# SSD_M_2_B-Key.net
KiCad netlist of a schematic drawn in Altium Designer
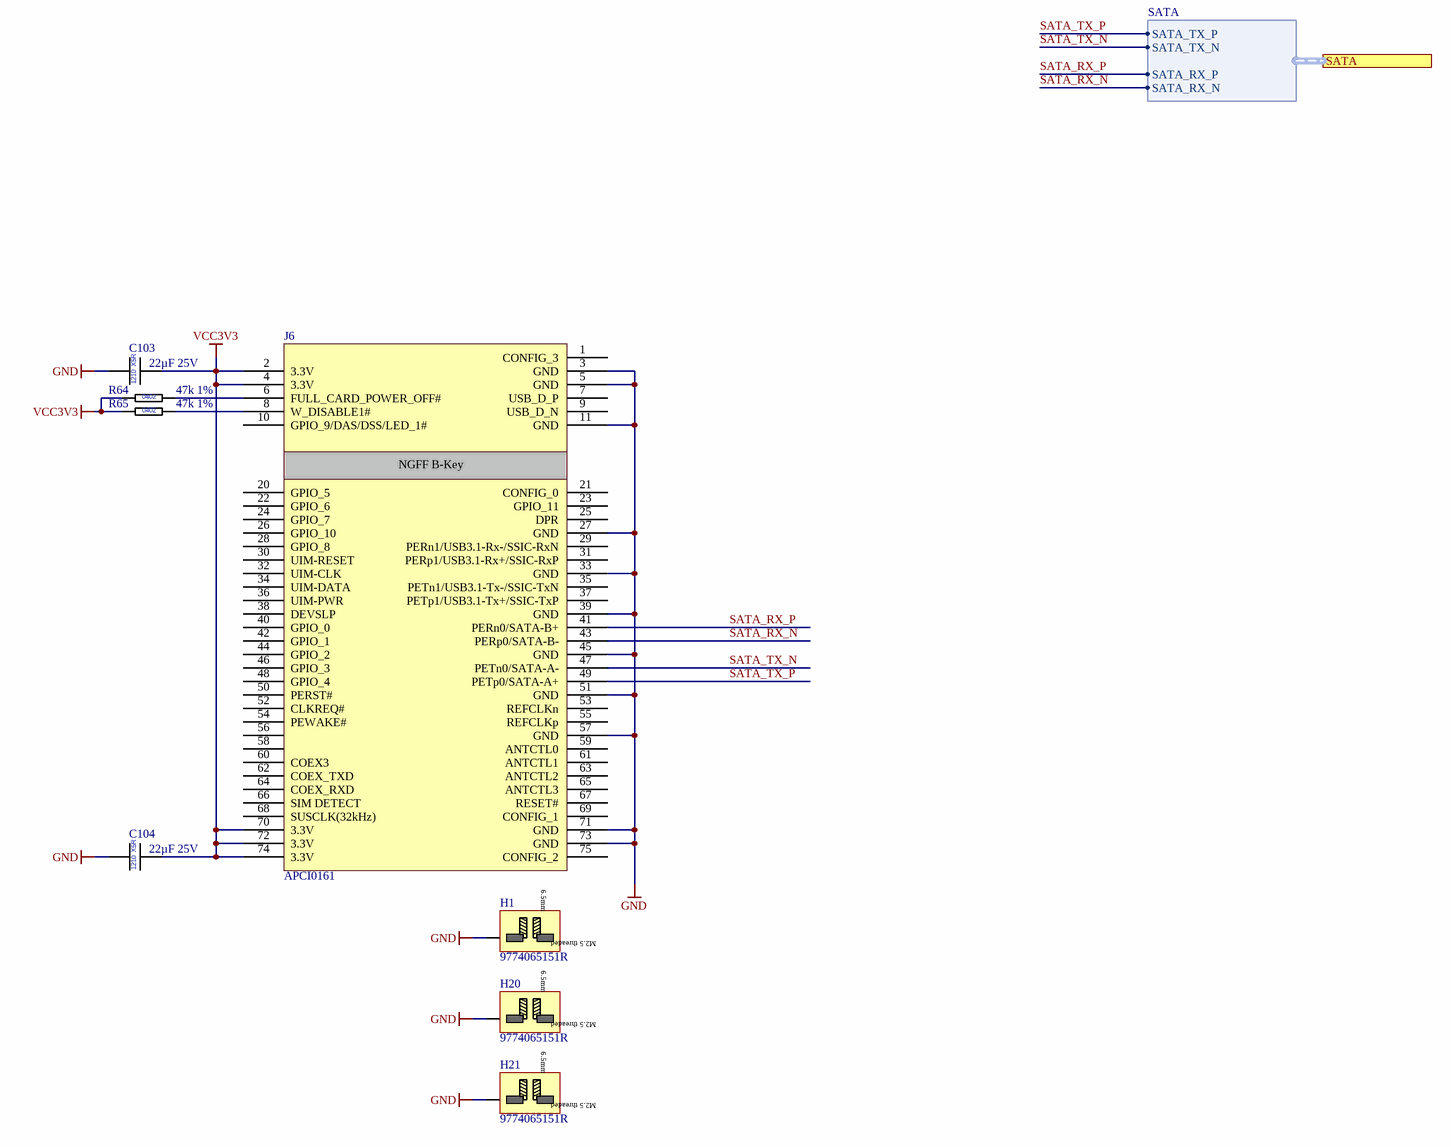
[diagram p0: SSD M.2_B-Key.SchDoc]

(export (version "E")
  (design (tool "Eeschema 10.0.6"))
  (components
    (comp (ref "C103")
      (value "22µF 25V")
      (footprint "Cap:CAP_1210")
      (description "Multilayer Ceramic Capacitors MLCC - SMD/SMT 1210 25VDC")
      (libsource (lib "Cap") (part "CAP_1210_22µF_25V"))
    )
    (comp (ref "C104")
      (value "22µF 25V")
      (footprint "Cap:CAP_1210")
      (description "Multilayer Ceramic Capacitors MLCC - SMD/SMT 1210 25VDC")
      (libsource (lib "Cap") (part "CAP_1210_22µF_25V"))
    )
    (comp (ref "H1")
      (value "9774065151R")
      (footprint "Electro_Mech:9774065151R")
      (description "Würth Standoff M2.5 h:6.5mm 9774065151R")
      (libsource (lib "Electro_Mech") (part "Würth Standoff M2.5 h{colon}6.5mm"))
    )
    (comp (ref "H20")
      (value "9774065151R")
      (footprint "Electro_Mech:9774065151R")
      (description "Würth Standoff M2.5 h:6.5mm 9774065151R")
      (libsource (lib "Electro_Mech") (part "Würth Standoff M2.5 h{colon}6.5mm"))
    )
    (comp (ref "H21")
      (value "9774065151R")
      (footprint "Electro_Mech:9774065151R")
      (description "Würth Standoff M2.5 h:6.5mm 9774065151R")
      (libsource (lib "Electro_Mech") (part "Würth Standoff M2.5 h{colon}6.5mm"))
    )
    (comp (ref "J6")
      (value "APCI0161")
      (footprint "conn:APCI0161-P001A")
      (description "NGFF B-Key Card Edge Connector 8.5mm Height")
      (libsource (lib "Conn") (part "APCI0161-NGFF B-Key Card Edge Connector 8.5mm Height"))
    )
    (comp (ref "R64")
      (value "47k 1%")
      (footprint "Res:RES_0402_L")
      (description "Thick Film Resistors - SMD 47kOhm 1%")
      (libsource (lib "Res") (part "RES_0402_47k_1%"))
    )
    (comp (ref "R65")
      (value "47k 1%")
      (footprint "Res:RES_0402_L")
      (description "Thick Film Resistors - SMD 47kOhm 1%")
      (libsource (lib "Res") (part "RES_0402_47k_1%"))
    )
  )
  (nets
    (net (code "2") (name "/SATA_RX_N") (class "Default")
      (node (ref "J6") (pin "43") (pinfunction "PERp0/SATA-B-_43") (pintype "passive"))
    )
    (net (code "3") (name "/SATA_RX_P") (class "Default")
      (node (ref "J6") (pin "41") (pinfunction "PERn0/SATA-B+_41") (pintype "passive"))
    )
    (net (code "4") (name "/SATA_TX_N") (class "Default")
      (node (ref "J6") (pin "47") (pinfunction "PETn0/SATA-A-_47") (pintype "passive"))
    )
    (net (code "5") (name "/SATA_TX_P") (class "Default")
      (node (ref "J6") (pin "49") (pinfunction "PETp0/SATA-A+_49") (pintype "passive"))
    )
    (net (code "7") (name "GND") (class "Default")
      (node (ref "C103") (pin "1") (pinfunction "1_1") (pintype "passive"))
      (node (ref "C104") (pin "1") (pinfunction "1_1") (pintype "passive"))
      (node (ref "H1") (pin "1") (pinfunction "1_1") (pintype "passive"))
      (node (ref "H20") (pin "1") (pinfunction "1_1") (pintype "passive"))
      (node (ref "H21") (pin "1") (pinfunction "1_1") (pintype "passive"))
      (node (ref "J6") (pin "11") (pinfunction "GND_11") (pintype "passive"))
      (node (ref "J6") (pin "27") (pinfunction "GND_27") (pintype "passive"))
      (node (ref "J6") (pin "3") (pinfunction "GND_3") (pintype "passive"))
      (node (ref "J6") (pin "33") (pinfunction "GND_33") (pintype "passive"))
      (node (ref "J6") (pin "39") (pinfunction "GND_39") (pintype "passive"))
      (node (ref "J6") (pin "45") (pinfunction "GND_45") (pintype "passive"))
      (node (ref "J6") (pin "5") (pinfunction "GND_5") (pintype "passive"))
      (node (ref "J6") (pin "51") (pinfunction "GND_51") (pintype "passive"))
      (node (ref "J6") (pin "57") (pinfunction "GND_57") (pintype "passive"))
      (node (ref "J6") (pin "71") (pinfunction "GND_71") (pintype "passive"))
      (node (ref "J6") (pin "73") (pinfunction "GND_73") (pintype "passive"))
    )
    (net (code "8") (name "Net-(J6-FULL_CARD_POWER_OFF#)") (class "Default")
      (node (ref "J6") (pin "6") (pinfunction "FULL_CARD_POWER_OFF#_6") (pintype "passive"))
      (node (ref "R64") (pin "2") (pinfunction "2_2") (pintype "passive"))
    )
    (net (code "9") (name "Net-(J6-W_DISABLE1#)") (class "Default")
      (node (ref "J6") (pin "8") (pinfunction "W_DISABLE1#_8") (pintype "passive"))
      (node (ref "R65") (pin "2") (pinfunction "2_2") (pintype "passive"))
    )
    (net (code "10") (name "VCC3V3") (class "Default")
      (node (ref "C103") (pin "2") (pinfunction "2_2") (pintype "passive"))
      (node (ref "C104") (pin "2") (pinfunction "2_2") (pintype "passive"))
      (node (ref "J6") (pin "2") (pinfunction "3.3V_2") (pintype "passive"))
      (node (ref "J6") (pin "4") (pinfunction "3.3V_4") (pintype "passive"))
      (node (ref "J6") (pin "70") (pinfunction "3.3V_70") (pintype "passive"))
      (node (ref "J6") (pin "72") (pinfunction "3.3V_72") (pintype "passive"))
      (node (ref "J6") (pin "74") (pinfunction "3.3V_74") (pintype "passive"))
      (node (ref "R64") (pin "1") (pinfunction "1_1") (pintype "passive"))
      (node (ref "R65") (pin "1") (pinfunction "1_1") (pintype "passive"))
    )
    (net (code "11") (name "unconnected-(J6-ANTCTL0-Pad59)") (class "Default")
      (node (ref "J6") (pin "59") (pinfunction "ANTCTL0_59") (pintype "passive"))
    )
    (net (code "12") (name "unconnected-(J6-ANTCTL1-Pad61)") (class "Default")
      (node (ref "J6") (pin "61") (pinfunction "ANTCTL1_61") (pintype "passive"))
    )
    (net (code "13") (name "unconnected-(J6-ANTCTL2-Pad63)") (class "Default")
      (node (ref "J6") (pin "63") (pinfunction "ANTCTL2_63") (pintype "passive"))
    )
    (net (code "14") (name "unconnected-(J6-ANTCTL3-Pad65)") (class "Default")
      (node (ref "J6") (pin "65") (pinfunction "ANTCTL3_65") (pintype "passive"))
    )
    (net (code "15") (name "unconnected-(J6-CLKREQ#-Pad52)") (class "Default")
      (node (ref "J6") (pin "52") (pinfunction "CLKREQ#_52") (pintype "passive"))
    )
    (net (code "16") (name "unconnected-(J6-COEX3-Pad60)") (class "Default")
      (node (ref "J6") (pin "60") (pinfunction "COEX3_60") (pintype "passive"))
    )
    (net (code "17") (name "unconnected-(J6-COEX_RXD-Pad64)") (class "Default")
      (node (ref "J6") (pin "64") (pinfunction "COEX_RXD_64") (pintype "passive"))
    )
    (net (code "18") (name "unconnected-(J6-COEX_TXD-Pad62)") (class "Default")
      (node (ref "J6") (pin "62") (pinfunction "COEX_TXD_62") (pintype "passive"))
    )
    (net (code "19") (name "unconnected-(J6-CONFIG_0-Pad21)") (class "Default")
      (node (ref "J6") (pin "21") (pinfunction "CONFIG_0_21") (pintype "passive"))
    )
    (net (code "20") (name "unconnected-(J6-CONFIG_1-Pad69)") (class "Default")
      (node (ref "J6") (pin "69") (pinfunction "CONFIG_1_69") (pintype "passive"))
    )
    (net (code "21") (name "unconnected-(J6-CONFIG_2-Pad75)") (class "Default")
      (node (ref "J6") (pin "75") (pinfunction "CONFIG_2_75") (pintype "passive"))
    )
    (net (code "22") (name "unconnected-(J6-CONFIG_3-Pad1)") (class "Default")
      (node (ref "J6") (pin "1") (pinfunction "CONFIG_3_1") (pintype "passive"))
    )
    (net (code "23") (name "unconnected-(J6-DEVSLP-Pad38)") (class "Default")
      (node (ref "J6") (pin "38") (pinfunction "DEVSLP_38") (pintype "passive"))
    )
    (net (code "24") (name "unconnected-(J6-DPR-Pad25)") (class "Default")
      (node (ref "J6") (pin "25") (pinfunction "DPR_25") (pintype "passive"))
    )
    (net (code "25") (name "unconnected-(J6-GPIO_0-Pad40)") (class "Default")
      (node (ref "J6") (pin "40") (pinfunction "GPIO_0_40") (pintype "passive"))
    )
    (net (code "26") (name "unconnected-(J6-GPIO_1-Pad42)") (class "Default")
      (node (ref "J6") (pin "42") (pinfunction "GPIO_1_42") (pintype "passive"))
    )
    (net (code "27") (name "unconnected-(J6-GPIO_2-Pad44)") (class "Default")
      (node (ref "J6") (pin "44") (pinfunction "GPIO_2_44") (pintype "passive"))
    )
    (net (code "28") (name "unconnected-(J6-GPIO_3-Pad46)") (class "Default")
      (node (ref "J6") (pin "46") (pinfunction "GPIO_3_46") (pintype "passive"))
    )
    (net (code "29") (name "unconnected-(J6-GPIO_4-Pad48)") (class "Default")
      (node (ref "J6") (pin "48") (pinfunction "GPIO_4_48") (pintype "passive"))
    )
    (net (code "30") (name "unconnected-(J6-GPIO_5-Pad20)") (class "Default")
      (node (ref "J6") (pin "20") (pinfunction "GPIO_5_20") (pintype "passive"))
    )
    (net (code "31") (name "unconnected-(J6-GPIO_6-Pad22)") (class "Default")
      (node (ref "J6") (pin "22") (pinfunction "GPIO_6_22") (pintype "passive"))
    )
    (net (code "32") (name "unconnected-(J6-GPIO_7-Pad24)") (class "Default")
      (node (ref "J6") (pin "24") (pinfunction "GPIO_7_24") (pintype "passive"))
    )
    (net (code "33") (name "unconnected-(J6-GPIO_8-Pad28)") (class "Default")
      (node (ref "J6") (pin "28") (pinfunction "GPIO_8_28") (pintype "passive"))
    )
    (net (code "34") (name "unconnected-(J6-GPIO_9{slash}DAS{slash}DSS{slash}LED_1#-Pad10)") (class "Default")
      (node (ref "J6") (pin "10") (pinfunction "GPIO_9/DAS/DSS/LED_1#_10") (pintype "passive"))
    )
    (net (code "35") (name "unconnected-(J6-GPIO_10-Pad26)") (class "Default")
      (node (ref "J6") (pin "26") (pinfunction "GPIO_10_26") (pintype "passive"))
    )
    (net (code "36") (name "unconnected-(J6-GPIO_11-Pad23)") (class "Default")
      (node (ref "J6") (pin "23") (pinfunction "GPIO_11_23") (pintype "passive"))
    )
    (net (code "37") (name "unconnected-(J6-PERST#-Pad50)") (class "Default")
      (node (ref "J6") (pin "50") (pinfunction "PERST#_50") (pintype "passive"))
    )
    (net (code "38") (name "unconnected-(J6-PERn1{slash}USB3.1-Rx-{slash}SSIC-RxN-Pad29)") (class "Default")
      (node (ref "J6") (pin "29") (pinfunction "PERn1/USB3.1-Rx-/SSIC-RxN_29") (pintype "passive"))
    )
    (net (code "39") (name "unconnected-(J6-PERp1{slash}USB3.1-Rx+{slash}SSIC-RxP-Pad31)") (class "Default")
      (node (ref "J6") (pin "31") (pinfunction "PERp1/USB3.1-Rx+/SSIC-RxP_31") (pintype "passive"))
    )
    (net (code "40") (name "unconnected-(J6-PETn1{slash}USB3.1-Tx-{slash}SSIC-TxN-Pad35)") (class "Default")
      (node (ref "J6") (pin "35") (pinfunction "PETn1/USB3.1-Tx-/SSIC-TxN_35") (pintype "passive"))
    )
    (net (code "41") (name "unconnected-(J6-PETp1{slash}USB3.1-Tx+{slash}SSIC-TxP-Pad37)") (class "Default")
      (node (ref "J6") (pin "37") (pinfunction "PETp1/USB3.1-Tx+/SSIC-TxP_37") (pintype "passive"))
    )
    (net (code "42") (name "unconnected-(J6-PEWAKE#-Pad54)") (class "Default")
      (node (ref "J6") (pin "54") (pinfunction "PEWAKE#_54") (pintype "passive"))
    )
    (net (code "43") (name "unconnected-(J6-Pad56)") (class "Default")
      (node (ref "J6") (pin "56") (pintype "passive"))
    )
    (net (code "44") (name "unconnected-(J6-Pad58)") (class "Default")
      (node (ref "J6") (pin "58") (pintype "passive"))
    )
    (net (code "45") (name "unconnected-(J6-REFCLKn-Pad53)") (class "Default")
      (node (ref "J6") (pin "53") (pinfunction "REFCLKn_53") (pintype "passive"))
    )
    (net (code "46") (name "unconnected-(J6-REFCLKp-Pad55)") (class "Default")
      (node (ref "J6") (pin "55") (pinfunction "REFCLKp_55") (pintype "passive"))
    )
    (net (code "47") (name "unconnected-(J6-RESET#-Pad67)") (class "Default")
      (node (ref "J6") (pin "67") (pinfunction "RESET#_67") (pintype "passive"))
    )
    (net (code "48") (name "unconnected-(J6-SIM_DETECT-Pad66)") (class "Default")
      (node (ref "J6") (pin "66") (pinfunction "SIM_DETECT_66") (pintype "passive"))
    )
    (net (code "49") (name "unconnected-(J6-SUSCLK(32kHz)-Pad68)") (class "Default")
      (node (ref "J6") (pin "68") (pinfunction "SUSCLK(32kHz)_68") (pintype "passive"))
    )
    (net (code "50") (name "unconnected-(J6-UIM-CLK-Pad32)") (class "Default")
      (node (ref "J6") (pin "32") (pinfunction "UIM-CLK_32") (pintype "passive"))
    )
    (net (code "51") (name "unconnected-(J6-UIM-DATA-Pad34)") (class "Default")
      (node (ref "J6") (pin "34") (pinfunction "UIM-DATA_34") (pintype "passive"))
    )
    (net (code "52") (name "unconnected-(J6-UIM-PWR-Pad36)") (class "Default")
      (node (ref "J6") (pin "36") (pinfunction "UIM-PWR_36") (pintype "passive"))
    )
    (net (code "53") (name "unconnected-(J6-UIM-RESET-Pad30)") (class "Default")
      (node (ref "J6") (pin "30") (pinfunction "UIM-RESET_30") (pintype "passive"))
    )
    (net (code "54") (name "unconnected-(J6-USB_D_N-Pad9)") (class "Default")
      (node (ref "J6") (pin "9") (pinfunction "USB_D_N_9") (pintype "passive"))
    )
    (net (code "55") (name "unconnected-(J6-USB_D_P-Pad7)") (class "Default")
      (node (ref "J6") (pin "7") (pinfunction "USB_D_P_7") (pintype "passive"))
    )
  )
)
